# MachDoNuoc.net
KiCad netlist of a schematic drawn in Altium Designer
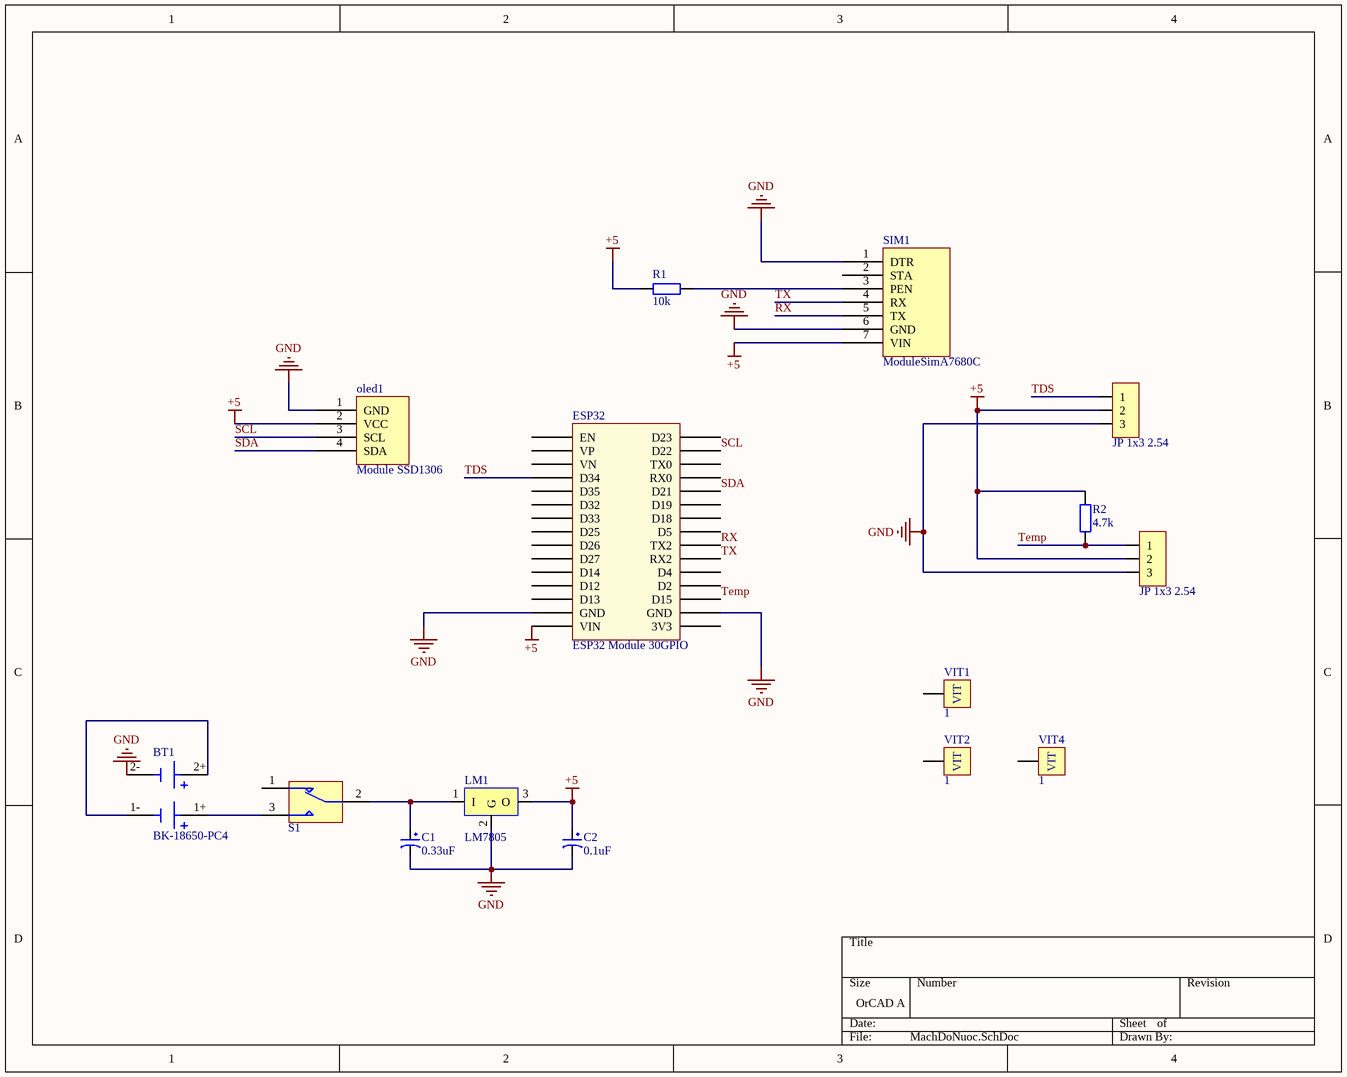
[diagram p0: MachDoNuoc.SchDoc]

(export (version "E")
  (design (tool "Eeschema 10.0.6"))
  (components
    (comp (ref "BT1")
      (value "BK-18650-PC4")
      (footprint "BAT_BK-18650-PC4")
      (description "Battery Holder (Open) 18650 2 Cell PC Pin")
      (libsource (lib "MrKoi_Lib_Sch") (part "BK-18650-PC4"))
    )
    (comp (ref "C1")
      (value "0.33uF")
      (footprint "tu hoa 5mm")
      (description "Cắm")
      (libsource (lib "Tu dien") (part "Tu Hoa 0.33uF 50V 5x11"))
    )
    (comp (ref "C2")
      (value "0.1uF")
      (footprint "tu hoa 5mm")
      (description "Cắm")
      (libsource (lib "Tu dien") (part "Tu Hoa 0.1uF 50V 5x11"))
    )
    (comp (ref "ESP32")
      (value "ESP32 Module 30GPIO")
      (footprint "ESP32 Module 30GPIO_v2")
      (libsource (lib "Module1") (part "ESP32 Module 30GPIO"))
    )
    (comp (ref "JP1")
      (value "JP 1x3 2.54")
      (footprint "JP 1x3 DT")
      (description "Cắm")
      (libsource (lib "Jump") (part "JP 1x3 2.54 Duc Thang"))
    )
    (comp (ref "JP2")
      (value "JP 1x3 2.54")
      (footprint "JP 1x3 DT")
      (description "Cắm")
      (libsource (lib "Jump") (part "JP 1x3 2.54 Duc Thang"))
    )
    (comp (ref "LM1")
      (value "LM7805")
      (footprint "TO220H1")
      (description "IC REG LDO 5V 1A TO220-3")
      (libsource (lib "IC") (part "LM78xx"))
    )
    (comp (ref "oled1")
      (value "Module SSD1306")
      (footprint "Module SSD1306")
      (libsource (lib "MrKoi_Lib_Sch") (part "Module SSD1306"))
    )
    (comp (ref "R1")
      (value "10k")
      (footprint "tro vach 1w")
      (description "Cắm")
      (libsource (lib "Dien Tro") (part "Tro Vach 1W 5% 10k"))
    )
    (comp (ref "R2")
      (value "4.7k")
      (footprint "tro vach 1w")
      (description "Cắm")
      (libsource (lib "Dien Tro") (part "Tro Vach 1W 5% 4.7k"))
    )
    (comp (ref "S1")
      (value "Switch SPDT_Subminiator")
      (footprint "SPDT Subminiator")
      (description "Subminiator SPDT Switch")
      (libsource (lib "iDr.ALTIUM") (part "Switch SPDT_Subminiator"))
    )
    (comp (ref "SIM1")
      (value "ModuleSimA7680C")
      (footprint "JP 1X7 CT")
      (libsource (lib "MyLibrary") (part "ModuleSimA7680C"))
    )
    (comp (ref "VIT1")
      (value "1")
      (footprint "Screw octagon 3.81mm")
      (description "Vit xuyen lo")
      (libsource (lib "Connector") (part "VIT"))
    )
    (comp (ref "VIT2")
      (value "1")
      (footprint "Screw octagon 3.81mm")
      (description "Vit xuyen lo")
      (libsource (lib "Connector") (part "VIT"))
    )
    (comp (ref "VIT4")
      (value "1")
      (footprint "Screw octagon 3.81mm")
      (description "Vit xuyen lo")
      (libsource (lib "Connector") (part "VIT"))
    )
  )
  (nets
    (net (code "1") (name "+5") (class "Default")
      (node (ref "C2") (pin "1") (pinfunction "1_1") (pintype "passive"))
      (node (ref "ESP32") (pin "30") (pinfunction "VIN_30") (pintype "passive"))
      (node (ref "JP1") (pin "2") (pinfunction "2_2") (pintype "passive"))
      (node (ref "JP2") (pin "2") (pinfunction "2_2") (pintype "passive"))
      (node (ref "LM1") (pin "3") (pinfunction "O_3") (pintype "power_in"))
      (node (ref "R1") (pin "1") (pinfunction "1_1") (pintype "passive"))
      (node (ref "R2") (pin "2") (pinfunction "2_2") (pintype "passive"))
      (node (ref "SIM1") (pin "7") (pinfunction "VIN_7") (pintype "passive"))
      (node (ref "oled1") (pin "2") (pinfunction "VCC_2") (pintype "passive"))
    )
    (net (code "2") (name "/RX") (class "Default")
      (node (ref "ESP32") (pin "9") (pinfunction "TX2_9") (pintype "passive"))
      (node (ref "SIM1") (pin "5") (pinfunction "TX_5") (pintype "passive"))
    )
    (net (code "3") (name "/SCL") (class "Default")
      (node (ref "ESP32") (pin "2") (pinfunction "D22_2") (pintype "passive"))
      (node (ref "oled1") (pin "3") (pinfunction "SCL_3") (pintype "passive"))
    )
    (net (code "4") (name "/SDA") (class "Default")
      (node (ref "ESP32") (pin "5") (pinfunction "D21_5") (pintype "passive"))
      (node (ref "oled1") (pin "4") (pinfunction "SDA_4") (pintype "passive"))
    )
    (net (code "5") (name "/TDS") (class "Default")
      (node (ref "ESP32") (pin "19") (pinfunction "D34_19") (pintype "passive"))
      (node (ref "JP1") (pin "1") (pinfunction "1_1") (pintype "passive"))
    )
    (net (code "6") (name "/TX") (class "Default")
      (node (ref "ESP32") (pin "10") (pinfunction "RX2_10") (pintype "passive"))
      (node (ref "SIM1") (pin "4") (pinfunction "RX_4") (pintype "passive"))
    )
    (net (code "7") (name "/Temp") (class "Default")
      (node (ref "ESP32") (pin "13") (pinfunction "D15_13") (pintype "passive"))
      (node (ref "JP2") (pin "1") (pinfunction "1_1") (pintype "passive"))
      (node (ref "R2") (pin "1") (pinfunction "1_1") (pintype "passive"))
    )
    (net (code "8") (name "GND") (class "Default")
      (node (ref "BT1") (pin "2-") (pinfunction "2-_2-") (pintype "passive"))
      (node (ref "C1") (pin "2") (pinfunction "2_2") (pintype "passive"))
      (node (ref "C2") (pin "2") (pinfunction "2_2") (pintype "passive"))
      (node (ref "ESP32") (pin "14") (pinfunction "GND_14") (pintype "passive"))
      (node (ref "ESP32") (pin "29") (pinfunction "GND_29") (pintype "passive"))
      (node (ref "JP1") (pin "3") (pinfunction "3_3") (pintype "passive"))
      (node (ref "JP2") (pin "3") (pinfunction "3_3") (pintype "passive"))
      (node (ref "LM1") (pin "2") (pinfunction "G_2") (pintype "power_in"))
      (node (ref "SIM1") (pin "1") (pinfunction "DTR_1") (pintype "passive"))
      (node (ref "SIM1") (pin "6") (pinfunction "GND_6") (pintype "passive"))
      (node (ref "oled1") (pin "1") (pinfunction "GND_1") (pintype "passive"))
    )
    (net (code "9") (name "Net-(BT1-Pad1+)") (class "Default")
      (node (ref "BT1") (pin "1+") (pinfunction "1+_1+") (pintype "passive"))
      (node (ref "S1") (pin "3") (pinfunction "3_3") (pintype "passive"))
    )
    (net (code "10") (name "Net-(BT1-Pad1-)") (class "Default")
      (node (ref "BT1") (pin "1-") (pinfunction "1-_1-") (pintype "passive"))
      (node (ref "BT1") (pin "2+") (pinfunction "2+_2+") (pintype "passive"))
    )
    (net (code "11") (name "Net-(LM1-I)") (class "Default")
      (node (ref "C1") (pin "1") (pinfunction "1_1") (pintype "passive"))
      (node (ref "LM1") (pin "1") (pinfunction "I_1") (pintype "power_in"))
      (node (ref "S1") (pin "2") (pinfunction "2_2") (pintype "passive"))
    )
    (net (code "12") (name "Net-(SIM1-PEN)") (class "Default")
      (node (ref "R1") (pin "2") (pinfunction "2_2") (pintype "passive"))
      (node (ref "SIM1") (pin "3") (pinfunction "PEN_3") (pintype "passive"))
    )
    (net (code "13") (name "unconnected-(ESP32-3V3-Pad15)") (class "Default")
      (node (ref "ESP32") (pin "15") (pinfunction "3V3_15") (pintype "passive"))
    )
    (net (code "14") (name "unconnected-(ESP32-D2-Pad12)") (class "Default")
      (node (ref "ESP32") (pin "12") (pinfunction "D2_12") (pintype "passive"))
    )
    (net (code "15") (name "unconnected-(ESP32-D4-Pad11)") (class "Default")
      (node (ref "ESP32") (pin "11") (pinfunction "D4_11") (pintype "passive"))
    )
    (net (code "16") (name "unconnected-(ESP32-D5-Pad8)") (class "Default")
      (node (ref "ESP32") (pin "8") (pinfunction "D5_8") (pintype "passive"))
    )
    (net (code "17") (name "unconnected-(ESP32-D12-Pad27)") (class "Default")
      (node (ref "ESP32") (pin "27") (pinfunction "D12_27") (pintype "passive"))
    )
    (net (code "18") (name "unconnected-(ESP32-D13-Pad28)") (class "Default")
      (node (ref "ESP32") (pin "28") (pinfunction "D13_28") (pintype "passive"))
    )
    (net (code "19") (name "unconnected-(ESP32-D14-Pad26)") (class "Default")
      (node (ref "ESP32") (pin "26") (pinfunction "D14_26") (pintype "passive"))
    )
    (net (code "20") (name "unconnected-(ESP32-D18-Pad7)") (class "Default")
      (node (ref "ESP32") (pin "7") (pinfunction "D18_7") (pintype "passive"))
    )
    (net (code "21") (name "unconnected-(ESP32-D19-Pad6)") (class "Default")
      (node (ref "ESP32") (pin "6") (pinfunction "D19_6") (pintype "passive"))
    )
    (net (code "22") (name "unconnected-(ESP32-D23-Pad1)") (class "Default")
      (node (ref "ESP32") (pin "1") (pinfunction "D23_1") (pintype "passive"))
    )
    (net (code "23") (name "unconnected-(ESP32-D25-Pad23)") (class "Default")
      (node (ref "ESP32") (pin "23") (pinfunction "D25_23") (pintype "passive"))
    )
    (net (code "24") (name "unconnected-(ESP32-D26-Pad24)") (class "Default")
      (node (ref "ESP32") (pin "24") (pinfunction "D26_24") (pintype "passive"))
    )
    (net (code "25") (name "unconnected-(ESP32-D27-Pad25)") (class "Default")
      (node (ref "ESP32") (pin "25") (pinfunction "D27_25") (pintype "passive"))
    )
    (net (code "26") (name "unconnected-(ESP32-D32-Pad21)") (class "Default")
      (node (ref "ESP32") (pin "21") (pinfunction "D32_21") (pintype "passive"))
    )
    (net (code "27") (name "unconnected-(ESP32-D33-Pad22)") (class "Default")
      (node (ref "ESP32") (pin "22") (pinfunction "D33_22") (pintype "passive"))
    )
    (net (code "28") (name "unconnected-(ESP32-D35-Pad20)") (class "Default")
      (node (ref "ESP32") (pin "20") (pinfunction "D35_20") (pintype "passive"))
    )
    (net (code "29") (name "unconnected-(ESP32-EN-Pad16)") (class "Default")
      (node (ref "ESP32") (pin "16") (pinfunction "EN_16") (pintype "passive"))
    )
    (net (code "30") (name "unconnected-(ESP32-RX0-Pad4)") (class "Default")
      (node (ref "ESP32") (pin "4") (pinfunction "RX0_4") (pintype "passive"))
    )
    (net (code "31") (name "unconnected-(ESP32-TX0-Pad3)") (class "Default")
      (node (ref "ESP32") (pin "3") (pinfunction "TX0_3") (pintype "passive"))
    )
    (net (code "32") (name "unconnected-(ESP32-VN-Pad18)") (class "Default")
      (node (ref "ESP32") (pin "18") (pinfunction "VN_18") (pintype "passive"))
    )
    (net (code "33") (name "unconnected-(ESP32-VP-Pad17)") (class "Default")
      (node (ref "ESP32") (pin "17") (pinfunction "VP_17") (pintype "passive"))
    )
    (net (code "34") (name "unconnected-(S1-Pad1)") (class "Default")
      (node (ref "S1") (pin "1") (pinfunction "1_1") (pintype "passive"))
    )
    (net (code "35") (name "unconnected-(SIM1-STA-Pad2)") (class "Default")
      (node (ref "SIM1") (pin "2") (pinfunction "STA_2") (pintype "passive"))
    )
    (net (code "36") (name "unconnected-(VIT1-Pad1)") (class "Default")
      (node (ref "VIT1") (pin "1") (pinfunction "1_1") (pintype "passive"))
    )
    (net (code "37") (name "unconnected-(VIT2-Pad1)") (class "Default")
      (node (ref "VIT2") (pin "1") (pinfunction "1_1") (pintype "passive"))
    )
    (net (code "38") (name "unconnected-(VIT4-Pad1)") (class "Default")
      (node (ref "VIT4") (pin "1") (pinfunction "1_1") (pintype "passive"))
    )
  )
)
